# NodeMCU.net
KiCad netlist of a schematic drawn in Altium Designer
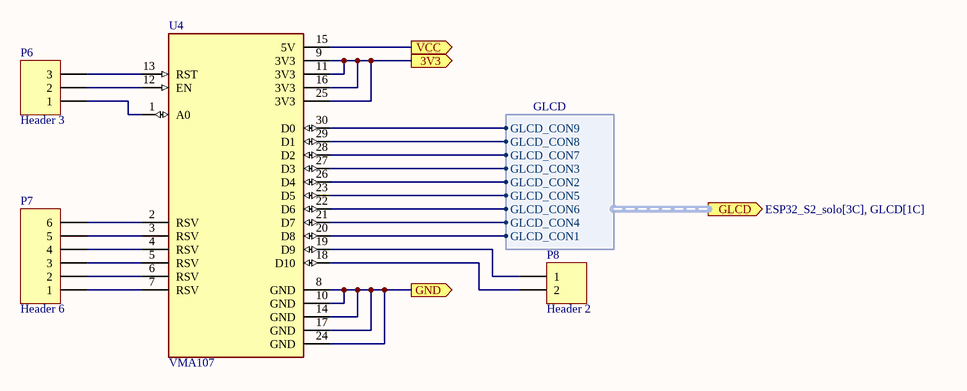
[diagram p0: NodeMCU.SchDoc]

(export (version "E")
  (design (tool "Eeschema 10.0.6"))
  (components
    (comp (ref "P6")
      (value "Header 3")
      (footprint "HDR1X3")
      (description "Header, 3-Pin")
      (fields (field (name "PUBLISHER") "Altium Limited"))
      (libsource (lib "Miscellaneous Connectors") (part "Header 3"))
    )
    (comp (ref "P7")
      (value "Header 6")
      (footprint "HDR1X6")
      (description "Header, 6-Pin")
      (fields (field (name "PUBLISHER") "Altium Limited"))
      (libsource (lib "Miscellaneous Connectors") (part "Header 6"))
    )
    (comp (ref "P8")
      (value "Header 2")
      (footprint "HDR1X2")
      (description "Header, 2-Pin")
      (fields (field (name "PUBLISHER") "Altium Limited"))
      (libsource (lib "Miscellaneous Connectors") (part "Header 2"))
    )
    (comp (ref "U4")
      (value "VMA107")
      (footprint "MODULE_VMA107")
      (description "NodeMCU V2 Lua Based ESP8266 Development Board")
      (fields (field (name "MF") "{'manufacturer': u'Velleman'}"))
      (libsource (lib "SnapEDA_Library") (part "VMA107"))
    )
  )
  (nets
    (net (code "2") (name "/3V3") (class "Default")
      (node (ref "U4") (pin "11") (pinfunction "3V3_11") (pintype "power_in"))
      (node (ref "U4") (pin "16") (pinfunction "3V3_16") (pintype "power_in"))
      (node (ref "U4") (pin "25") (pinfunction "3V3_25") (pintype "power_in"))
      (node (ref "U4") (pin "9") (pinfunction "3V3_9") (pintype "power_in"))
    )
    (net (code "3") (name "/GLCD_CON1") (class "Default")
      (node (ref "U4") (pin "20") (pinfunction "D8_20") (pintype "bidirectional"))
    )
    (net (code "4") (name "/GLCD_CON2") (class "Default")
      (node (ref "U4") (pin "26") (pinfunction "D4_26") (pintype "bidirectional"))
    )
    (net (code "5") (name "/GLCD_CON3") (class "Default")
      (node (ref "U4") (pin "27") (pinfunction "D3_27") (pintype "bidirectional"))
    )
    (net (code "6") (name "/GLCD_CON4") (class "Default")
      (node (ref "U4") (pin "21") (pinfunction "D7_21") (pintype "bidirectional"))
    )
    (net (code "7") (name "/GLCD_CON5") (class "Default")
      (node (ref "U4") (pin "23") (pinfunction "D5_23") (pintype "bidirectional"))
    )
    (net (code "8") (name "/GLCD_CON6") (class "Default")
      (node (ref "U4") (pin "22") (pinfunction "D6_22") (pintype "bidirectional"))
    )
    (net (code "9") (name "/GLCD_CON7") (class "Default")
      (node (ref "U4") (pin "28") (pinfunction "D2_28") (pintype "bidirectional"))
    )
    (net (code "10") (name "/GLCD_CON8") (class "Default")
      (node (ref "U4") (pin "29") (pinfunction "D1_29") (pintype "bidirectional"))
    )
    (net (code "11") (name "/GLCD_CON9") (class "Default")
      (node (ref "U4") (pin "30") (pinfunction "D0_30") (pintype "bidirectional"))
    )
    (net (code "12") (name "/GND") (class "Default")
      (node (ref "U4") (pin "10") (pinfunction "GND_10") (pintype "power_in"))
      (node (ref "U4") (pin "14") (pinfunction "GND_14") (pintype "power_in"))
      (node (ref "U4") (pin "17") (pinfunction "GND_17") (pintype "power_in"))
      (node (ref "U4") (pin "24") (pinfunction "GND_24") (pintype "power_in"))
      (node (ref "U4") (pin "8") (pinfunction "GND_8") (pintype "power_in"))
    )
    (net (code "13") (name "/VCC") (class "Default")
      (node (ref "U4") (pin "15") (pinfunction "5V_15") (pintype "power_in"))
    )
    (net (code "15") (name "Net-(P7-Pad1)") (class "Default")
      (node (ref "P7") (pin "1") (pinfunction "1_1") (pintype "passive"))
      (node (ref "U4") (pin "7") (pinfunction "RSV_7") (pintype "passive"))
    )
    (net (code "16") (name "Net-(P7-Pad2)") (class "Default")
      (node (ref "P7") (pin "2") (pinfunction "2_2") (pintype "passive"))
      (node (ref "U4") (pin "6") (pinfunction "RSV_6") (pintype "passive"))
    )
    (net (code "17") (name "Net-(P7-Pad3)") (class "Default")
      (node (ref "P7") (pin "3") (pinfunction "3_3") (pintype "passive"))
      (node (ref "U4") (pin "5") (pinfunction "RSV_5") (pintype "passive"))
    )
    (net (code "18") (name "Net-(P7-Pad4)") (class "Default")
      (node (ref "P7") (pin "4") (pinfunction "4_4") (pintype "passive"))
      (node (ref "U4") (pin "4") (pinfunction "RSV_4") (pintype "passive"))
    )
    (net (code "19") (name "Net-(P7-Pad5)") (class "Default")
      (node (ref "P7") (pin "5") (pinfunction "5_5") (pintype "passive"))
      (node (ref "U4") (pin "3") (pinfunction "RSV_3") (pintype "passive"))
    )
    (net (code "20") (name "Net-(P7-Pad6)") (class "Default")
      (node (ref "P7") (pin "6") (pinfunction "6_6") (pintype "passive"))
      (node (ref "U4") (pin "2") (pinfunction "RSV_2") (pintype "passive"))
    )
    (net (code "21") (name "Net-(U4-A0)") (class "Default")
      (node (ref "P6") (pin "1") (pinfunction "1_1") (pintype "passive"))
      (node (ref "U4") (pin "1") (pinfunction "A0_1") (pintype "bidirectional"))
    )
    (net (code "22") (name "Net-(U4-D9)") (class "Default")
      (node (ref "P8") (pin "1") (pinfunction "1_1") (pintype "passive"))
      (node (ref "U4") (pin "19") (pinfunction "D9_19") (pintype "bidirectional"))
    )
    (net (code "23") (name "Net-(U4-D10)") (class "Default")
      (node (ref "P8") (pin "2") (pinfunction "2_2") (pintype "passive"))
      (node (ref "U4") (pin "18") (pinfunction "D10_18") (pintype "bidirectional"))
    )
    (net (code "24") (name "Net-(U4-EN)") (class "Default")
      (node (ref "P6") (pin "2") (pinfunction "2_2") (pintype "passive"))
      (node (ref "U4") (pin "12") (pinfunction "EN_12") (pintype "input"))
    )
    (net (code "25") (name "Net-(U4-RST)") (class "Default")
      (node (ref "P6") (pin "3") (pinfunction "3_3") (pintype "passive"))
      (node (ref "U4") (pin "13") (pinfunction "RST_13") (pintype "input"))
    )
  )
)
